# WL-FPGA.net
KiCad netlist of a schematic drawn in Altium Designer
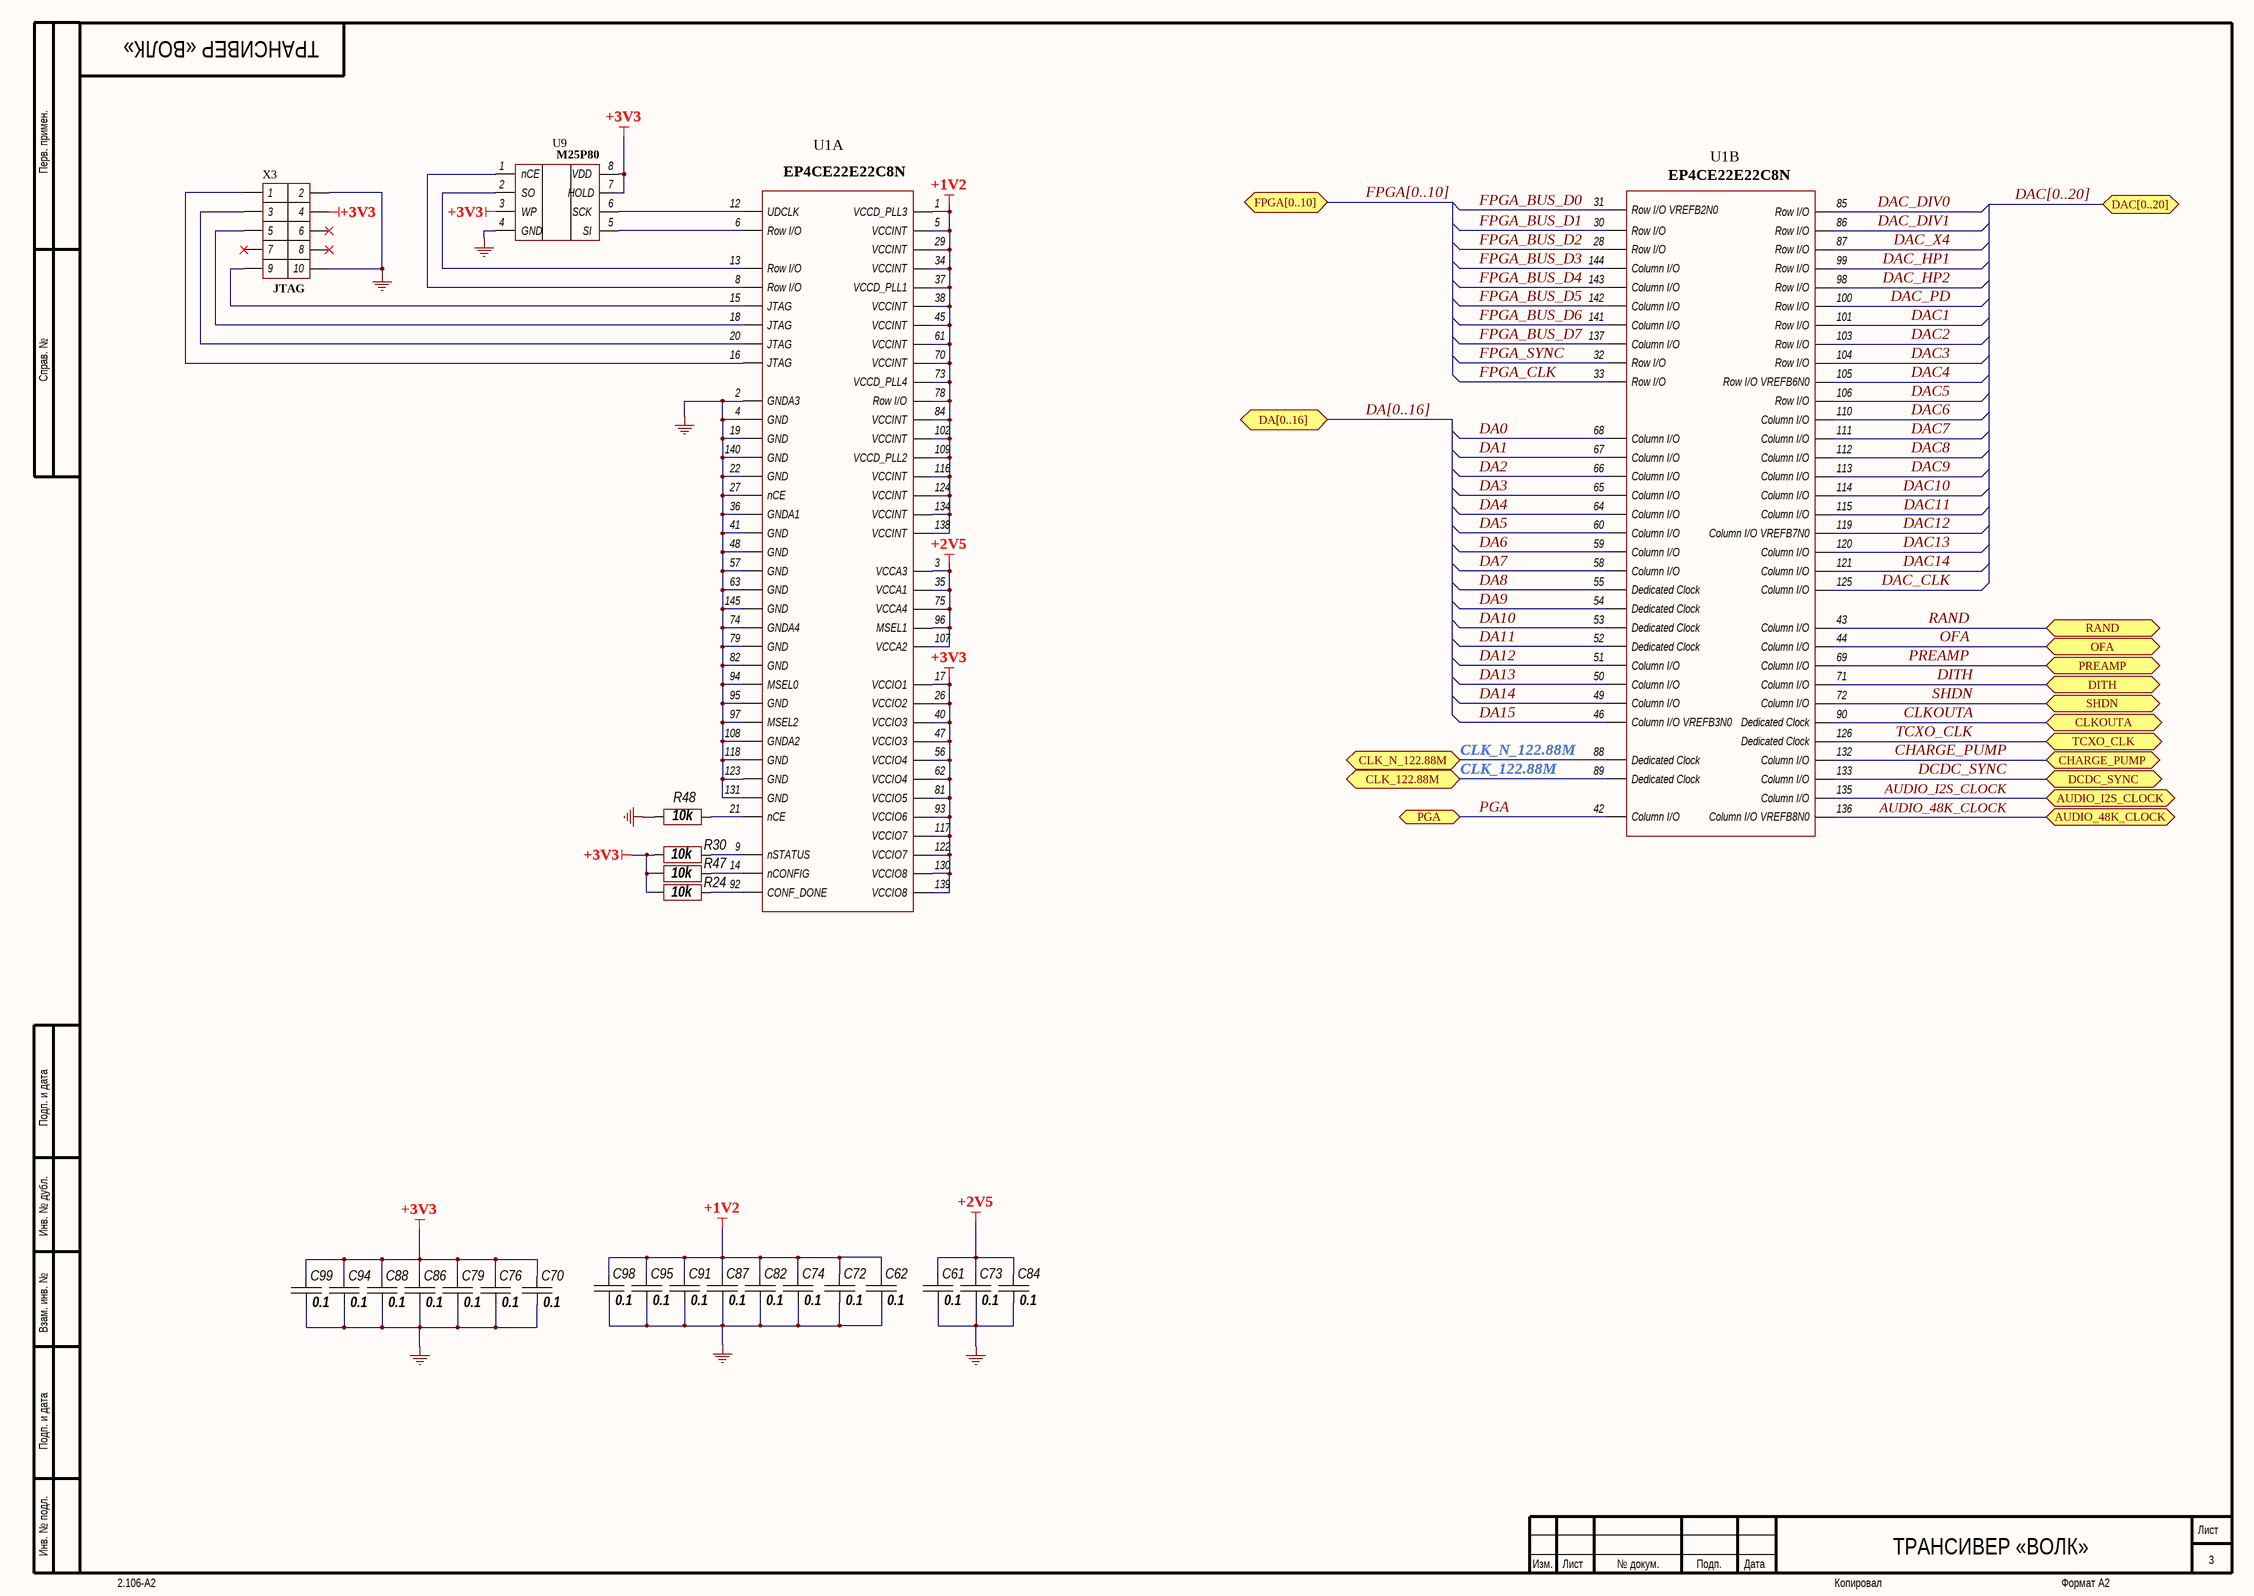
[diagram p0: WL-FPGA.SchDoc]

(export (version "E")
  (design (tool "Eeschema 10.0.6"))
  (components
    (comp (ref "C61")
      (value "0.1")
      (footprint "standard:CH0805C")
      (libsource (lib "Discrete") (part "Capacitor"))
    )
    (comp (ref "C62")
      (value "0.1")
      (footprint "standard:CH0805C")
      (libsource (lib "Discrete") (part "Capacitor"))
    )
    (comp (ref "C70")
      (value "0.1")
      (footprint "standard:CH0805C")
      (libsource (lib "Discrete") (part "Capacitor"))
    )
    (comp (ref "C72")
      (value "0.1")
      (footprint "standard:CH0805C")
      (libsource (lib "Discrete") (part "Capacitor"))
    )
    (comp (ref "C73")
      (value "0.1")
      (footprint "standard:CH0805C")
      (libsource (lib "Discrete") (part "Capacitor"))
    )
    (comp (ref "C74")
      (value "0.1")
      (footprint "standard:CH0805C")
      (libsource (lib "Discrete") (part "Capacitor"))
    )
    (comp (ref "C76")
      (value "0.1")
      (footprint "standard:CH0805C")
      (libsource (lib "Discrete") (part "Capacitor"))
    )
    (comp (ref "C79")
      (value "0.1")
      (footprint "standard:CH0805C")
      (libsource (lib "Discrete") (part "Capacitor"))
    )
    (comp (ref "C82")
      (value "0.1")
      (footprint "standard:CH0805C")
      (libsource (lib "Discrete") (part "Capacitor"))
    )
    (comp (ref "C84")
      (value "0.1")
      (footprint "standard:CH0805C")
      (libsource (lib "Discrete") (part "Capacitor"))
    )
    (comp (ref "C86")
      (value "0.1")
      (footprint "standard:CH0805C")
      (libsource (lib "Discrete") (part "Capacitor"))
    )
    (comp (ref "C87")
      (value "0.1")
      (footprint "standard:CH0805C")
      (libsource (lib "Discrete") (part "Capacitor"))
    )
    (comp (ref "C88")
      (value "0.1")
      (footprint "standard:CH0805C")
      (libsource (lib "Discrete") (part "Capacitor"))
    )
    (comp (ref "C91")
      (value "0.1")
      (footprint "standard:CH0805C")
      (libsource (lib "Discrete") (part "Capacitor"))
    )
    (comp (ref "C94")
      (value "0.1")
      (footprint "standard:CH0805C")
      (libsource (lib "Discrete") (part "Capacitor"))
    )
    (comp (ref "C95")
      (value "0.1")
      (footprint "standard:CH0805C")
      (libsource (lib "Discrete") (part "Capacitor"))
    )
    (comp (ref "C98")
      (value "0.1")
      (footprint "standard:CH0805C")
      (libsource (lib "Discrete") (part "Capacitor"))
    )
    (comp (ref "C99")
      (value "0.1")
      (footprint "standard:CH0805C")
      (libsource (lib "Discrete") (part "Capacitor"))
    )
    (comp (ref "R24")
      (value "10k")
      (footprint "standard:CH0805R")
      (libsource (lib "Discrete") (part "Resistor"))
    )
    (comp (ref "R30")
      (value "10k")
      (footprint "standard:CH0805R")
      (libsource (lib "Discrete") (part "Resistor"))
    )
    (comp (ref "R47")
      (value "10k")
      (footprint "standard:CH0805R")
      (libsource (lib "Discrete") (part "Resistor"))
    )
    (comp (ref "R48")
      (value "10k")
      (footprint "standard:CH0805R")
      (libsource (lib "Discrete") (part "Resistor"))
    )
    (comp (ref "U1")
      (value "EP4CE22E22C8N")
      (footprint "144-QFN")
      (libsource (lib "Digital") (part "EP4CE22E22C8N-№1"))
    )
    (comp (ref "U9") (value "M25P80") (footprint "8-SOIC") (libsource (lib "Digital") (part "M25P80")))
    (comp (ref "X3") (value "JTAG") (footprint "CON: PLD-10") (libsource (lib "Connectors") (part "Jtag")))
  )
  (nets
    (net (code "20") (name "+1V2") (class "Default")
      (node (ref "C62") (pin "2") (pinfunction "2_2") (pintype "power_in"))
      (node (ref "C72") (pin "2") (pinfunction "2_2") (pintype "power_in"))
      (node (ref "C74") (pin "2") (pinfunction "2_2") (pintype "power_in"))
      (node (ref "C82") (pin "2") (pinfunction "2_2") (pintype "power_in"))
      (node (ref "C87") (pin "2") (pinfunction "2_2") (pintype "power_in"))
      (node (ref "C91") (pin "2") (pinfunction "2_2") (pintype "power_in"))
      (node (ref "C95") (pin "2") (pinfunction "2_2") (pintype "power_in"))
      (node (ref "C98") (pin "2") (pinfunction "2_2") (pintype "power_in"))
      (node (ref "U1") (pin "1") (pinfunction "VCCD_PLL3_1") (pintype "power_in"))
      (node (ref "U1") (pin "102") (pinfunction "VCCINT_102") (pintype "passive"))
      (node (ref "U1") (pin "109") (pinfunction "VCCD_PLL2_109") (pintype "passive"))
      (node (ref "U1") (pin "116") (pinfunction "VCCINT_116") (pintype "passive"))
      (node (ref "U1") (pin "124") (pinfunction "VCCINT_124") (pintype "passive"))
      (node (ref "U1") (pin "134") (pinfunction "VCCINT_134") (pintype "passive"))
      (node (ref "U1") (pin "138") (pinfunction "VCCINT_138") (pintype "passive"))
      (node (ref "U1") (pin "29") (pinfunction "VCCINT_29") (pintype "power_in"))
      (node (ref "U1") (pin "34") (pinfunction "VCCINT_34") (pintype "power_in"))
      (node (ref "U1") (pin "37") (pinfunction "VCCD_PLL1_37") (pintype "passive"))
      (node (ref "U1") (pin "38") (pinfunction "VCCINT_38") (pintype "passive"))
      (node (ref "U1") (pin "45") (pinfunction "VCCINT_45") (pintype "passive"))
      (node (ref "U1") (pin "5") (pinfunction "VCCINT_5") (pintype "power_in"))
      (node (ref "U1") (pin "61") (pinfunction "VCCINT_61") (pintype "passive"))
      (node (ref "U1") (pin "70") (pinfunction "VCCINT_70") (pintype "passive"))
      (node (ref "U1") (pin "73") (pinfunction "VCCD_PLL4_73") (pintype "passive"))
      (node (ref "U1") (pin "78") (pinfunction "Row_I/O_78") (pintype "passive"))
      (node (ref "U1") (pin "84") (pinfunction "VCCINT_84") (pintype "passive"))
    )
    (net (code "21") (name "+2V5") (class "Default")
      (node (ref "C61") (pin "2") (pinfunction "2_2") (pintype "power_in"))
      (node (ref "C73") (pin "2") (pinfunction "2_2") (pintype "power_in"))
      (node (ref "C84") (pin "2") (pinfunction "2_2") (pintype "power_in"))
      (node (ref "U1") (pin "107") (pinfunction "VCCA2_107") (pintype "passive"))
      (node (ref "U1") (pin "3") (pinfunction "VCCA3_3") (pintype "passive"))
      (node (ref "U1") (pin "35") (pinfunction "VCCA1_35") (pintype "passive"))
      (node (ref "U1") (pin "75") (pinfunction "VCCA4_75") (pintype "passive"))
      (node (ref "U1") (pin "96") (pinfunction "MSEL1_96") (pintype "passive"))
    )
    (net (code "22") (name "+3V3") (class "Default")
      (node (ref "C70") (pin "2") (pinfunction "2_2") (pintype "power_in"))
      (node (ref "C76") (pin "2") (pinfunction "2_2") (pintype "power_in"))
      (node (ref "C79") (pin "2") (pinfunction "2_2") (pintype "power_in"))
      (node (ref "C86") (pin "2") (pinfunction "2_2") (pintype "power_in"))
      (node (ref "C88") (pin "2") (pinfunction "2_2") (pintype "power_in"))
      (node (ref "C94") (pin "2") (pinfunction "2_2") (pintype "power_in"))
      (node (ref "C99") (pin "2") (pinfunction "2_2") (pintype "power_in"))
      (node (ref "R24") (pin "2") (pinfunction "2_2") (pintype "passive"))
      (node (ref "R30") (pin "2") (pinfunction "2_2") (pintype "passive"))
      (node (ref "R47") (pin "2") (pinfunction "2_2") (pintype "passive"))
      (node (ref "U1") (pin "117") (pinfunction "VCCIO7_117") (pintype "passive"))
      (node (ref "U1") (pin "122") (pinfunction "VCCIO7_122") (pintype "passive"))
      (node (ref "U1") (pin "130") (pinfunction "VCCIO8_130") (pintype "passive"))
      (node (ref "U1") (pin "139") (pinfunction "VCCIO8_139") (pintype "passive"))
      (node (ref "U1") (pin "17") (pinfunction "VCCIO1_17") (pintype "passive"))
      (node (ref "U1") (pin "26") (pinfunction "VCCIO2_26") (pintype "passive"))
      (node (ref "U1") (pin "40") (pinfunction "VCCIO3_40") (pintype "passive"))
      (node (ref "U1") (pin "47") (pinfunction "VCCIO3_47") (pintype "passive"))
      (node (ref "U1") (pin "56") (pinfunction "VCCIO4_56") (pintype "passive"))
      (node (ref "U1") (pin "62") (pinfunction "VCCIO4_62") (pintype "passive"))
      (node (ref "U1") (pin "81") (pinfunction "VCCIO5_81") (pintype "passive"))
      (node (ref "U1") (pin "93") (pinfunction "VCCIO6_93") (pintype "passive"))
      (node (ref "U9") (pin "3") (pinfunction "WP_3") (pintype "passive"))
      (node (ref "U9") (pin "7") (pinfunction "HOLD_7") (pintype "passive"))
      (node (ref "U9") (pin "8") (pinfunction "VDD_8") (pintype "passive"))
      (node (ref "X3") (pin "4") (pinfunction "4_4") (pintype "power_in"))
    )
    (net (code "23") (name "/AUDIO_48K_CLOCK") (class "Default")
      (node (ref "U1") (pin "136") (pinfunction "Column_I/O_VREFB8N0_136") (pintype "power_in"))
    )
    (net (code "24") (name "/AUDIO_I2S_CLOCK") (class "Default")
      (node (ref "U1") (pin "135") (pinfunction "Column_I/O_135") (pintype "power_in"))
    )
    (net (code "25") (name "/CHARGE_PUMP") (class "Default")
      (node (ref "U1") (pin "132") (pinfunction "Column_I/O_132") (pintype "power_in"))
    )
    (net (code "26") (name "/CLKOUTA") (class "Default")
      (node (ref "U1") (pin "90") (pinfunction "Dedicated_Clock_90") (pintype "power_in"))
    )
    (net (code "27") (name "/CLK_122.88M") (class "Default")
      (node (ref "U1") (pin "89") (pinfunction "Dedicated_Clock_89") (pintype "passive"))
    )
    (net (code "28") (name "/CLK_N_122.88M") (class "Default")
      (node (ref "U1") (pin "88") (pinfunction "Dedicated_Clock_88") (pintype "passive"))
    )
    (net (code "29") (name "/DA0") (class "Default")
      (node (ref "U1") (pin "68") (pinfunction "Column_I/O_68") (pintype "passive"))
    )
    (net (code "30") (name "/DA1") (class "Default")
      (node (ref "U1") (pin "67") (pinfunction "Column_I/O_67") (pintype "passive"))
    )
    (net (code "31") (name "/DA2") (class "Default")
      (node (ref "U1") (pin "66") (pinfunction "Column_I/O_66") (pintype "passive"))
    )
    (net (code "32") (name "/DA3") (class "Default")
      (node (ref "U1") (pin "65") (pinfunction "Column_I/O_65") (pintype "passive"))
    )
    (net (code "33") (name "/DA4") (class "Default")
      (node (ref "U1") (pin "64") (pinfunction "Column_I/O_64") (pintype "passive"))
    )
    (net (code "34") (name "/DA5") (class "Default")
      (node (ref "U1") (pin "60") (pinfunction "Column_I/O_60") (pintype "passive"))
    )
    (net (code "35") (name "/DA6") (class "Default")
      (node (ref "U1") (pin "59") (pinfunction "Column_I/O_59") (pintype "passive"))
    )
    (net (code "36") (name "/DA7") (class "Default")
      (node (ref "U1") (pin "58") (pinfunction "Column_I/O_58") (pintype "passive"))
    )
    (net (code "37") (name "/DA8") (class "Default")
      (node (ref "U1") (pin "55") (pinfunction "Dedicated_Clock_55") (pintype "passive"))
    )
    (net (code "38") (name "/DA9") (class "Default")
      (node (ref "U1") (pin "54") (pinfunction "Dedicated_Clock_54") (pintype "passive"))
    )
    (net (code "39") (name "/DA10") (class "Default")
      (node (ref "U1") (pin "53") (pinfunction "Dedicated_Clock_53") (pintype "passive"))
    )
    (net (code "40") (name "/DA11") (class "Default")
      (node (ref "U1") (pin "52") (pinfunction "Dedicated_Clock_52") (pintype "passive"))
    )
    (net (code "41") (name "/DA12") (class "Default")
      (node (ref "U1") (pin "51") (pinfunction "Column_I/O_51") (pintype "passive"))
    )
    (net (code "42") (name "/DA13") (class "Default")
      (node (ref "U1") (pin "50") (pinfunction "Column_I/O_50") (pintype "passive"))
    )
    (net (code "43") (name "/DA14") (class "Default")
      (node (ref "U1") (pin "49") (pinfunction "Column_I/O_49") (pintype "passive"))
    )
    (net (code "44") (name "/DA15") (class "Default")
      (node (ref "U1") (pin "46") (pinfunction "Column_I/O_VREFB3N0_46") (pintype "passive"))
    )
    (net (code "45") (name "/DAC1") (class "Default")
      (node (ref "U1") (pin "101") (pinfunction "Row_I/O_101") (pintype "power_in"))
    )
    (net (code "46") (name "/DAC2") (class "Default")
      (node (ref "U1") (pin "103") (pinfunction "Row_I/O_103") (pintype "power_in"))
    )
    (net (code "47") (name "/DAC3") (class "Default")
      (node (ref "U1") (pin "104") (pinfunction "Row_I/O_104") (pintype "power_in"))
    )
    (net (code "48") (name "/DAC4") (class "Default")
      (node (ref "U1") (pin "105") (pinfunction "Row_I/O_VREFB6N0_105") (pintype "power_in"))
    )
    (net (code "49") (name "/DAC5") (class "Default")
      (node (ref "U1") (pin "106") (pinfunction "Row_I/O_106") (pintype "power_in"))
    )
    (net (code "50") (name "/DAC6") (class "Default")
      (node (ref "U1") (pin "110") (pinfunction "Column_I/O_110") (pintype "power_in"))
    )
    (net (code "51") (name "/DAC7") (class "Default")
      (node (ref "U1") (pin "111") (pinfunction "Column_I/O_111") (pintype "power_in"))
    )
    (net (code "52") (name "/DAC8") (class "Default")
      (node (ref "U1") (pin "112") (pinfunction "Column_I/O_112") (pintype "power_in"))
    )
    (net (code "53") (name "/DAC9") (class "Default")
      (node (ref "U1") (pin "113") (pinfunction "Column_I/O_113") (pintype "power_in"))
    )
    (net (code "54") (name "/DAC10") (class "Default")
      (node (ref "U1") (pin "114") (pinfunction "Column_I/O_114") (pintype "power_in"))
    )
    (net (code "55") (name "/DAC11") (class "Default")
      (node (ref "U1") (pin "115") (pinfunction "Column_I/O_115") (pintype "power_in"))
    )
    (net (code "56") (name "/DAC12") (class "Default")
      (node (ref "U1") (pin "119") (pinfunction "Column_I/O_VREFB7N0_119") (pintype "power_in"))
    )
    (net (code "57") (name "/DAC13") (class "Default")
      (node (ref "U1") (pin "120") (pinfunction "Column_I/O_120") (pintype "power_in"))
    )
    (net (code "58") (name "/DAC14") (class "Default")
      (node (ref "U1") (pin "121") (pinfunction "Column_I/O_121") (pintype "power_in"))
    )
    (net (code "60") (name "/DAC_CLK") (class "Default")
      (node (ref "U1") (pin "125") (pinfunction "Column_I/O_125") (pintype "power_in"))
    )
    (net (code "61") (name "/DAC_DIV0") (class "Default")
      (node (ref "U1") (pin "85") (pinfunction "Row_I/O_85") (pintype "power_in"))
    )
    (net (code "62") (name "/DAC_DIV1") (class "Default")
      (node (ref "U1") (pin "86") (pinfunction "Row_I/O_86") (pintype "power_in"))
    )
    (net (code "63") (name "/DAC_HP1") (class "Default")
      (node (ref "U1") (pin "99") (pinfunction "Row_I/O_99") (pintype "power_in"))
    )
    (net (code "64") (name "/DAC_HP2") (class "Default")
      (node (ref "U1") (pin "98") (pinfunction "Row_I/O_98") (pintype "power_in"))
    )
    (net (code "65") (name "/DAC_PD") (class "Default")
      (node (ref "U1") (pin "100") (pinfunction "Row_I/O_100") (pintype "power_in"))
    )
    (net (code "66") (name "/DAC_X4") (class "Default")
      (node (ref "U1") (pin "87") (pinfunction "Row_I/O_87") (pintype "power_in"))
    )
    (net (code "68") (name "/DCDC_SYNC") (class "Default")
      (node (ref "U1") (pin "133") (pinfunction "Column_I/O_133") (pintype "power_in"))
    )
    (net (code "69") (name "/DITH") (class "Default")
      (node (ref "U1") (pin "71") (pinfunction "Column_I/O_71") (pintype "power_in"))
    )
    (net (code "71") (name "/FPGA_BUS_D0") (class "Default")
      (node (ref "U1") (pin "31") (pinfunction "Row_I/O_VREFB2N0_31") (pintype "passive"))
    )
    (net (code "72") (name "/FPGA_BUS_D1") (class "Default")
      (node (ref "U1") (pin "30") (pinfunction "Row_I/O_30") (pintype "passive"))
    )
    (net (code "73") (name "/FPGA_BUS_D2") (class "Default")
      (node (ref "U1") (pin "28") (pinfunction "Row_I/O_28") (pintype "passive"))
    )
    (net (code "74") (name "/FPGA_BUS_D3") (class "Default")
      (node (ref "U1") (pin "144") (pinfunction "Column_I/O_144") (pintype "passive"))
    )
    (net (code "75") (name "/FPGA_BUS_D4") (class "Default")
      (node (ref "U1") (pin "143") (pinfunction "Column_I/O_143") (pintype "passive"))
    )
    (net (code "76") (name "/FPGA_BUS_D5") (class "Default")
      (node (ref "U1") (pin "142") (pinfunction "Column_I/O_142") (pintype "passive"))
    )
    (net (code "77") (name "/FPGA_BUS_D6") (class "Default")
      (node (ref "U1") (pin "141") (pinfunction "Column_I/O_141") (pintype "passive"))
    )
    (net (code "78") (name "/FPGA_BUS_D7") (class "Default")
      (node (ref "U1") (pin "137") (pinfunction "Column_I/O_137") (pintype "passive"))
    )
    (net (code "79") (name "/FPGA_CLK") (class "Default")
      (node (ref "U1") (pin "33") (pinfunction "Row_I/O_33") (pintype "passive"))
    )
    (net (code "80") (name "/FPGA_SYNC") (class "Default")
      (node (ref "U1") (pin "32") (pinfunction "Row_I/O_32") (pintype "passive"))
    )
    (net (code "81") (name "/OFA") (class "Default")
      (node (ref "U1") (pin "44") (pinfunction "Column_I/O_44") (pintype "power_in"))
    )
    (net (code "82") (name "/PGA") (class "Default")
      (node (ref "U1") (pin "42") (pinfunction "Column_I/O_42") (pintype "passive"))
    )
    (net (code "83") (name "/PREAMP") (class "Default")
      (node (ref "U1") (pin "69") (pinfunction "Column_I/O_69") (pintype "power_in"))
    )
    (net (code "84") (name "/RAND") (class "Default")
      (node (ref "U1") (pin "43") (pinfunction "Column_I/O_43") (pintype "power_in"))
    )
    (net (code "85") (name "/SHDN") (class "Default")
      (node (ref "U1") (pin "72") (pinfunction "Column_I/O_72") (pintype "power_in"))
    )
    (net (code "86") (name "/TCXO_CLK") (class "Default")
      (node (ref "U1") (pin "126") (pinfunction "Dedicated_Clock_126") (pintype "power_in"))
    )
    (net (code "87") (name "GND") (class "Default")
      (node (ref "C61") (pin "1") (pinfunction "1_1") (pintype "power_in"))
      (node (ref "C62") (pin "1") (pinfunction "1_1") (pintype "power_in"))
      (node (ref "C70") (pin "1") (pinfunction "1_1") (pintype "power_in"))
      (node (ref "C72") (pin "1") (pinfunction "1_1") (pintype "power_in"))
      (node (ref "C73") (pin "1") (pinfunction "1_1") (pintype "power_in"))
      (node (ref "C74") (pin "1") (pinfunction "1_1") (pintype "power_in"))
      (node (ref "C76") (pin "1") (pinfunction "1_1") (pintype "power_in"))
      (node (ref "C79") (pin "1") (pinfunction "1_1") (pintype "power_in"))
      (node (ref "C82") (pin "1") (pinfunction "1_1") (pintype "power_in"))
      (node (ref "C84") (pin "1") (pinfunction "1_1") (pintype "power_in"))
      (node (ref "C86") (pin "1") (pinfunction "1_1") (pintype "power_in"))
      (node (ref "C87") (pin "1") (pinfunction "1_1") (pintype "power_in"))
      (node (ref "C88") (pin "1") (pinfunction "1_1") (pintype "power_in"))
      (node (ref "C91") (pin "1") (pinfunction "1_1") (pintype "power_in"))
      (node (ref "C94") (pin "1") (pinfunction "1_1") (pintype "power_in"))
      (node (ref "C95") (pin "1") (pinfunction "1_1") (pintype "power_in"))
      (node (ref "C98") (pin "1") (pinfunction "1_1") (pintype "power_in"))
      (node (ref "C99") (pin "1") (pinfunction "1_1") (pintype "power_in"))
      (node (ref "R48") (pin "2") (pinfunction "2_2") (pintype "passive"))
      (node (ref "U1") (pin "108") (pinfunction "GNDA2_108") (pintype "passive"))
      (node (ref "U1") (pin "118") (pinfunction "GND_118") (pintype "passive"))
      (node (ref "U1") (pin "123") (pinfunction "GND_123") (pintype "passive"))
      (node (ref "U1") (pin "131") (pinfunction "GND_131") (pintype "passive"))
      (node (ref "U1") (pin "140") (pinfunction "GND_140") (pintype "passive"))
      (node (ref "U1") (pin "145") (pinfunction "GND_145") (pintype "passive"))
      (node (ref "U1") (pin "19") (pinfunction "GND_19") (pintype "passive"))
      (node (ref "U1") (pin "2") (pinfunction "GNDA3_2") (pintype "passive"))
      (node (ref "U1") (pin "22") (pinfunction "GND_22") (pintype "power_in"))
      (node (ref "U1") (pin "27") (pinfunction "nCE_27") (pintype "passive"))
      (node (ref "U1") (pin "36") (pinfunction "GNDA1_36") (pintype "passive"))
      (node (ref "U1") (pin "4") (pinfunction "GND_4") (pintype "passive"))
      (node (ref "U1") (pin "41") (pinfunction "GND_41") (pintype "passive"))
      (node (ref "U1") (pin "48") (pinfunction "GND_48") (pintype "passive"))
      (node (ref "U1") (pin "57") (pinfunction "GND_57") (pintype "passive"))
      (node (ref "U1") (pin "63") (pinfunction "GND_63") (pintype "passive"))
      (node (ref "U1") (pin "74") (pinfunction "GNDA4_74") (pintype "passive"))
      (node (ref "U1") (pin "79") (pinfunction "GND_79") (pintype "passive"))
      (node (ref "U1") (pin "82") (pinfunction "GND_82") (pintype "passive"))
      (node (ref "U1") (pin "94") (pinfunction "MSEL0_94") (pintype "passive"))
      (node (ref "U1") (pin "95") (pinfunction "GND_95") (pintype "passive"))
      (node (ref "U1") (pin "97") (pinfunction "MSEL2_97") (pintype "passive"))
      (node (ref "U9") (pin "4") (pinfunction "GND_4") (pintype "passive"))
      (node (ref "X3") (pin "10") (pinfunction "10_10") (pintype "power_in"))
      (node (ref "X3") (pin "2") (pinfunction "2_2") (pintype "power_in"))
    )
    (net (code "88") (name "Net-(R48-Pad1)") (class "Default")
      (node (ref "R48") (pin "1") (pinfunction "1_1") (pintype "passive"))
      (node (ref "U1") (pin "21") (pinfunction "nCE_21") (pintype "passive"))
    )
    (net (code "89") (name "Net-(U1A-CONF_DONE)") (class "Default")
      (node (ref "R24") (pin "1") (pinfunction "1_1") (pintype "passive"))
      (node (ref "U1") (pin "92") (pinfunction "CONF_DONE_92") (pintype "passive"))
    )
    (net (code "90") (name "Net-(U1A-JTAG-Pad15)") (class "Default")
      (node (ref "U1") (pin "15") (pinfunction "JTAG_15") (pintype "passive"))
      (node (ref "X3") (pin "9") (pinfunction "9_9") (pintype "power_in"))
    )
    (net (code "91") (name "Net-(U1A-JTAG-Pad16)") (class "Default")
      (node (ref "U1") (pin "16") (pinfunction "JTAG_16") (pintype "passive"))
      (node (ref "X3") (pin "1") (pinfunction "1_1") (pintype "passive"))
    )
    (net (code "92") (name "Net-(U1A-JTAG-Pad18)") (class "Default")
      (node (ref "U1") (pin "18") (pinfunction "JTAG_18") (pintype "passive"))
      (node (ref "X3") (pin "5") (pinfunction "5_5") (pintype "power_in"))
    )
    (net (code "93") (name "Net-(U1A-JTAG-Pad20)") (class "Default")
      (node (ref "U1") (pin "20") (pinfunction "JTAG_20") (pintype "passive"))
      (node (ref "X3") (pin "3") (pinfunction "3_3") (pintype "passive"))
    )
    (net (code "94") (name "Net-(U1A-UDCLK)") (class "Default")
      (node (ref "U1") (pin "12") (pinfunction "UDCLK_12") (pintype "passive"))
      (node (ref "U9") (pin "6") (pinfunction "SCK_6") (pintype "passive"))
    )
    (net (code "95") (name "Net-(U1A-nCONFIG)") (class "Default")
      (node (ref "R47") (pin "1") (pinfunction "1_1") (pintype "passive"))
      (node (ref "U1") (pin "14") (pinfunction "nCONFIG_14") (pintype "passive"))
    )
    (net (code "96") (name "Net-(U1A-nSTATUS)") (class "Default")
      (node (ref "R30") (pin "1") (pinfunction "1_1") (pintype "passive"))
      (node (ref "U1") (pin "9") (pinfunction "nSTATUS_9") (pintype "passive"))
    )
    (net (code "97") (name "Net-(U9-SI)") (class "Default")
      (node (ref "U1") (pin "6") (pinfunction "Row_I/O_6") (pintype "passive"))
      (node (ref "U9") (pin "5") (pinfunction "SI_5") (pintype "passive"))
    )
    (net (code "98") (name "Net-(U9-SO)") (class "Default")
      (node (ref "U1") (pin "13") (pinfunction "Row_I/O_13") (pintype "passive"))
      (node (ref "U9") (pin "2") (pinfunction "SO_2") (pintype "passive"))
    )
    (net (code "99") (name "Net-(U9-nCE)") (class "Default")
      (node (ref "U1") (pin "8") (pinfunction "Row_I/O_8") (pintype "passive"))
      (node (ref "U9") (pin "1") (pinfunction "nCE_1") (pintype "passive"))
    )
    (net (code "100") (name "unconnected-(X3-Pad6)") (class "Default")
      (node (ref "X3") (pin "6") (pinfunction "6_6") (pintype "power_in+no_connect"))
    )
    (net (code "101") (name "unconnected-(X3-Pad7)") (class "Default")
      (node (ref "X3") (pin "7") (pinfunction "7_7") (pintype "power_in+no_connect"))
    )
    (net (code "102") (name "unconnected-(X3-Pad8)") (class "Default")
      (node (ref "X3") (pin "8") (pinfunction "8_8") (pintype "power_in+no_connect"))
    )
  )
)
